# Heater.net
KiCad netlist of a schematic drawn in Altium Designer
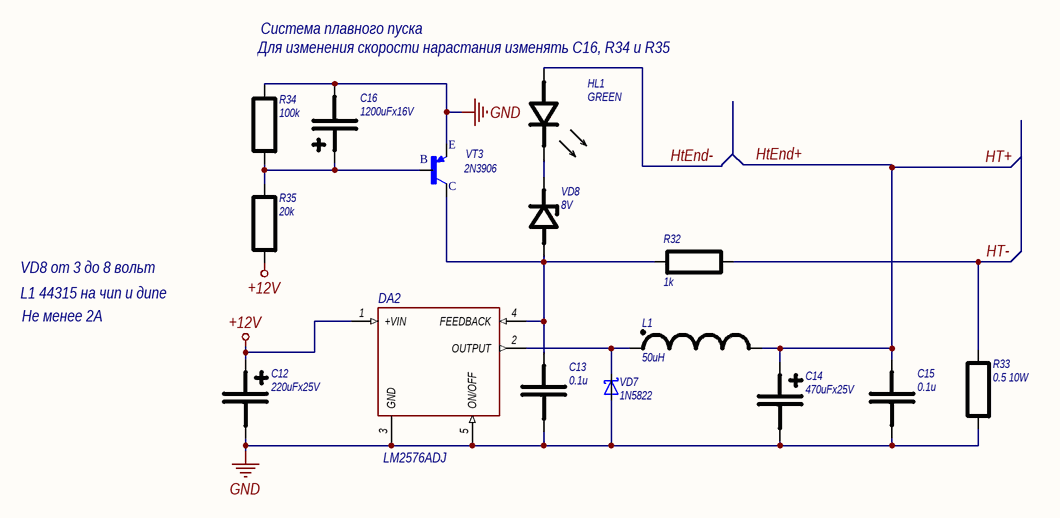
[diagram p0: Heater.SchDoc]

(export (version "E")
  (design (tool "Eeschema 10.0.6"))
  (components
    (comp (ref "C12")
      (value "220uFx25V")
      (footprint "C8x11.5")
      (description "SY025M0220A3F-0811")
      (libsource (lib "sobol_lib") (part "C220uFx25V YAGEO SY"))
    )
    (comp (ref "C13")
      (value "0.1u")
      (footprint "CR2012-0805")
      (libsource (lib "sobol_lib") (part "C0805-0.1u-X7R"))
    )
    (comp (ref "C14")
      (value "470uFx25V")
      (footprint "C10x16")
      (libsource (lib "sobol_lib") (part "C470uFx25V KF"))
    )
    (comp (ref "C15")
      (value "0.1u")
      (footprint "CR2012-0805")
      (libsource (lib "sobol_lib") (part "C0805-0.1u-X7R"))
    )
    (comp (ref "C16")
      (value "1200uFx16V")
      (footprint "C8x20")
      (libsource (lib "sobol_lib") (part "C1000uFx16V LZ"))
    )
    (comp (ref "DA2")
      (value "LM2576ADJ")
      (footprint "TO220-5")
      (description "<B>LM 2576 Adj</B><br> SIMPLE SWITCHER 3-A Step-Down Voltage Regulator")
      (fields (field (name "MF") "ON Semiconductor"))
      (libsource (lib "sobol_lib") (part "LM2576ADJ"))
    )
    (comp (ref "HL1")
      (value "GREEN")
      (footprint "CR3216-1206-LED")
      (libsource (lib "sobol_lib") (part "LED_GREEN_1206"))
    )
    (comp (ref "L1")
      (value "50uH")
      (footprint "RCH114")
      (libsource (lib "sobol_lib") (part "RCH114NP-221KB"))
    )
    (comp (ref "R32")
      (value "1k")
      (footprint "CR2012-0805")
      (libsource (lib "sobol_lib") (part "R0805-1k-5%"))
    )
    (comp (ref "R33") (value "0.5 10W") (footprint "R-1W") (libsource (lib "sobol_lib") (part "R-1W-5R1")))
    (comp (ref "R34")
      (value "100k")
      (footprint "CR2012-0805")
      (libsource (lib "sobol_lib") (part "R0805-100k-5%"))
    )
    (comp (ref "R35")
      (value "20k")
      (footprint "CR2012-0805")
      (libsource (lib "sobol_lib") (part "R0805-20k-5%"))
    )
    (comp (ref "VD7")
      (value "1N5822")
      (footprint "DIOAD2120W130L950D530P")
      (description "Diode Schottky 40V 3A Through Hole")
      (fields (field (name "MF") "ON Semiconductor"))
      (libsource (lib "sobol_lib") (part "1N5822"))
    )
    (comp (ref "VD8") (value "8V") (footprint "SOD-80") (libsource (lib "sobol_lib") (part "BZV55-C3V0")))
    (comp (ref "VT3")
      (value "2N3906")
      (footprint "TO-92")
      (description "TRANS PNP 40V 0.2A TO92")
      (fields (field (name "MF") "Diotec Semiconductor"))
      (libsource (lib "sobol_lib") (part "2N3906"))
    )
  )
  (nets
    (net (code "1") (name "+12V") (class "Default")
      (node (ref "C12") (pin "1") (pinfunction "1_1") (pintype "passive"))
      (node (ref "DA2") (pin "1") (pinfunction "+VIN_1") (pintype "input"))
      (node (ref "R35") (pin "1") (pinfunction "1_1") (pintype "passive"))
    )
    (net (code "2") (name "/HT+") (class "Default")
      (node (ref "C14") (pin "1") (pinfunction "1_1") (pintype "passive"))
      (node (ref "C15") (pin "1") (pinfunction "1_1") (pintype "passive"))
      (node (ref "L1") (pin "2") (pinfunction "2_2") (pintype "passive"))
    )
    (net (code "3") (name "/HT-") (class "Default")
      (node (ref "R32") (pin "2") (pinfunction "2_2") (pintype "passive"))
      (node (ref "R33") (pin "2") (pinfunction "2_2") (pintype "passive"))
    )
    (net (code "4") (name "/HtEnd-") (class "Default")
      (node (ref "HL1") (pin "1") (pinfunction "A_1") (pintype "passive"))
    )
    (net (code "5") (name "GND") (class "Default")
      (node (ref "C12") (pin "2") (pinfunction "2_2") (pintype "passive"))
      (node (ref "C13") (pin "2") (pinfunction "2_2") (pintype "passive"))
      (node (ref "C14") (pin "2") (pinfunction "2_2") (pintype "passive"))
      (node (ref "C15") (pin "2") (pinfunction "2_2") (pintype "passive"))
      (node (ref "C16") (pin "2") (pinfunction "2_2") (pintype "passive"))
      (node (ref "DA2") (pin "3") (pinfunction "GND_3") (pintype "power_in"))
      (node (ref "DA2") (pin "5") (pinfunction "ON/OFF_5") (pintype "input"))
      (node (ref "R33") (pin "1") (pinfunction "1_1") (pintype "passive"))
      (node (ref "R34") (pin "2") (pinfunction "2_2") (pintype "passive"))
      (node (ref "VD7") (pin "A") (pinfunction "A_A") (pintype "passive"))
      (node (ref "VT3") (pin "1") (pinfunction "E_1") (pintype "passive"))
    )
    (net (code "6") (name "Net-(DA2-FEEDBACK)") (class "Default")
      (node (ref "C13") (pin "1") (pinfunction "1_1") (pintype "passive"))
      (node (ref "DA2") (pin "4") (pinfunction "FEEDBACK_4") (pintype "input"))
      (node (ref "R32") (pin "1") (pinfunction "1_1") (pintype "passive"))
      (node (ref "VD8") (pin "1") (pinfunction "A_1") (pintype "passive"))
      (node (ref "VT3") (pin "3") (pinfunction "C_3") (pintype "passive"))
    )
    (net (code "7") (name "Net-(DA2-OUTPUT)") (class "Default")
      (node (ref "DA2") (pin "2") (pinfunction "OUTPUT_2") (pintype "output"))
      (node (ref "L1") (pin "1") (pinfunction "1_1") (pintype "passive"))
      (node (ref "VD7") (pin "C") (pinfunction "C_C") (pintype "passive"))
    )
    (net (code "8") (name "Net-(HL1-K)") (class "Default")
      (node (ref "HL1") (pin "2") (pinfunction "K_2") (pintype "passive"))
      (node (ref "VD8") (pin "2") (pinfunction "K_2") (pintype "passive"))
    )
    (net (code "9") (name "Net-(VT3-B)") (class "Default")
      (node (ref "C16") (pin "1") (pinfunction "1_1") (pintype "passive"))
      (node (ref "R34") (pin "1") (pinfunction "1_1") (pintype "passive"))
      (node (ref "R35") (pin "2") (pinfunction "2_2") (pintype "passive"))
      (node (ref "VT3") (pin "2") (pinfunction "B_2") (pintype "passive"))
    )
  )
)
